# VoltTap.net
KiCad netlist of a schematic drawn in Altium Designer
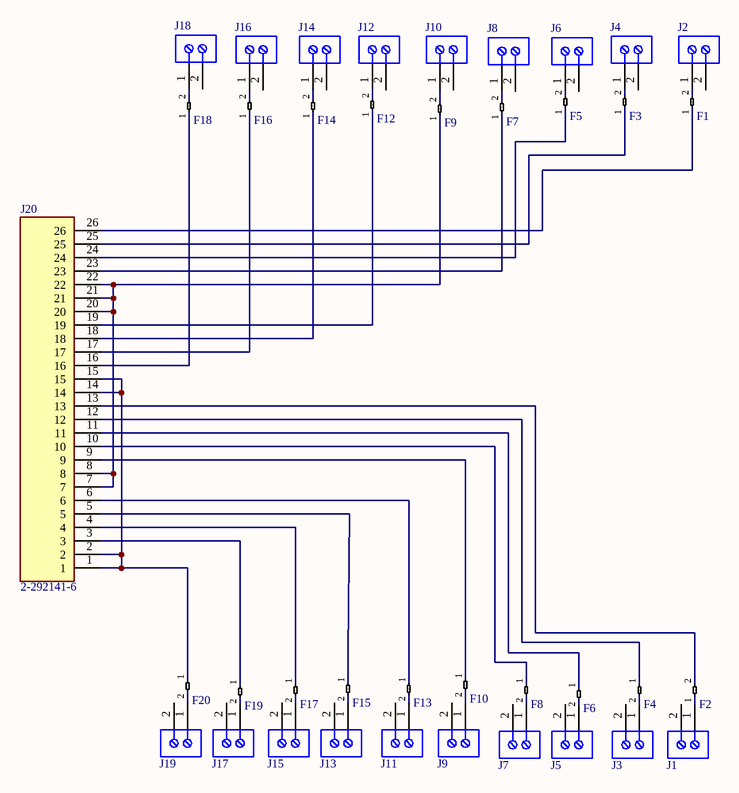
[diagram p0: VoltTap.SchDoc]

(export (version "E")
  (design (tool "Eeschema 10.0.6"))
  (components
    (comp (ref "F1") (value "C1T5") (footprint "C1T5") (libsource (lib "Integrated_Library1") (part "C1T5")))
    (comp (ref "F2") (value "C1T5") (footprint "C1T5") (libsource (lib "Integrated_Library1") (part "C1T5")))
    (comp (ref "F3") (value "C1T5") (footprint "C1T5") (libsource (lib "Integrated_Library1") (part "C1T5")))
    (comp (ref "F4") (value "C1T5") (footprint "C1T5") (libsource (lib "Integrated_Library1") (part "C1T5")))
    (comp (ref "F5") (value "C1T5") (footprint "C1T5") (libsource (lib "Integrated_Library1") (part "C1T5")))
    (comp (ref "F6") (value "C1T5") (footprint "C1T5") (libsource (lib "Integrated_Library1") (part "C1T5")))
    (comp (ref "F7") (value "C1T5") (footprint "C1T5") (libsource (lib "Integrated_Library1") (part "C1T5")))
    (comp (ref "F8") (value "C1T5") (footprint "C1T5") (libsource (lib "Integrated_Library1") (part "C1T5")))
    (comp (ref "F9") (value "C1T5") (footprint "C1T5") (libsource (lib "Integrated_Library1") (part "C1T5")))
    (comp (ref "F10") (value "C1T5") (footprint "C1T5") (libsource (lib "Integrated_Library1") (part "C1T5")))
    (comp (ref "F12") (value "C1T5") (footprint "C1T5") (libsource (lib "Integrated_Library1") (part "C1T5")))
    (comp (ref "F13") (value "C1T5") (footprint "C1T5") (libsource (lib "Integrated_Library1") (part "C1T5")))
    (comp (ref "F14") (value "C1T5") (footprint "C1T5") (libsource (lib "Integrated_Library1") (part "C1T5")))
    (comp (ref "F15") (value "C1T5") (footprint "C1T5") (libsource (lib "Integrated_Library1") (part "C1T5")))
    (comp (ref "F16") (value "C1T5") (footprint "C1T5") (libsource (lib "Integrated_Library1") (part "C1T5")))
    (comp (ref "F17") (value "C1T5") (footprint "C1T5") (libsource (lib "Integrated_Library1") (part "C1T5")))
    (comp (ref "F18") (value "C1T5") (footprint "C1T5") (libsource (lib "Integrated_Library1") (part "C1T5")))
    (comp (ref "F19") (value "C1T5") (footprint "C1T5") (libsource (lib "Integrated_Library1") (part "C1T5")))
    (comp (ref "F20") (value "C1T5") (footprint "C1T5") (libsource (lib "Integrated_Library1") (part "C1T5")))
    (comp (ref "J1")
      (value "691102710002")
      (footprint "691102710002")
      (description "Series 102 - 5.00 mm Horizontal Entry Modular with Pressure Clamp WR-TBL, 2 pin")
      (fields (field (name "MANUFACTURER") "Wurth Elektronik") (field (name "PUBLISHER") "WurthElektronik"))
      (libsource (lib "Altium Content Vault") (part "WE-CN-1P-F-TB2"))
    )
    (comp (ref "J2")
      (value "691102710002")
      (footprint "691102710002")
      (description "Series 102 - 5.00 mm Horizontal Entry Modular with Pressure Clamp WR-TBL, 2 pin")
      (fields (field (name "MANUFACTURER") "Wurth Elektronik") (field (name "PUBLISHER") "WurthElektronik"))
      (libsource (lib "Altium Content Vault") (part "WE-CN-1P-F-TB2"))
    )
    (comp (ref "J3")
      (value "691102710002")
      (footprint "691102710002")
      (description "Series 102 - 5.00 mm Horizontal Entry Modular with Pressure Clamp WR-TBL, 2 pin")
      (fields (field (name "MANUFACTURER") "Wurth Elektronik") (field (name "PUBLISHER") "WurthElektronik"))
      (libsource (lib "Altium Content Vault") (part "WE-CN-1P-F-TB2"))
    )
    (comp (ref "J4")
      (value "691102710002")
      (footprint "691102710002")
      (description "Series 102 - 5.00 mm Horizontal Entry Modular with Pressure Clamp WR-TBL, 2 pin")
      (fields (field (name "MANUFACTURER") "Wurth Elektronik") (field (name "PUBLISHER") "WurthElektronik"))
      (libsource (lib "Altium Content Vault") (part "WE-CN-1P-F-TB2"))
    )
    (comp (ref "J5")
      (value "691102710002")
      (footprint "691102710002")
      (description "Series 102 - 5.00 mm Horizontal Entry Modular with Pressure Clamp WR-TBL, 2 pin")
      (fields (field (name "MANUFACTURER") "Wurth Elektronik") (field (name "PUBLISHER") "WurthElektronik"))
      (libsource (lib "Altium Content Vault") (part "WE-CN-1P-F-TB2"))
    )
    (comp (ref "J6")
      (value "691102710002")
      (footprint "691102710002")
      (description "Series 102 - 5.00 mm Horizontal Entry Modular with Pressure Clamp WR-TBL, 2 pin")
      (fields (field (name "MANUFACTURER") "Wurth Elektronik") (field (name "PUBLISHER") "WurthElektronik"))
      (libsource (lib "Altium Content Vault") (part "WE-CN-1P-F-TB2"))
    )
    (comp (ref "J7")
      (value "691102710002")
      (footprint "691102710002")
      (description "Series 102 - 5.00 mm Horizontal Entry Modular with Pressure Clamp WR-TBL, 2 pin")
      (fields (field (name "MANUFACTURER") "Wurth Elektronik") (field (name "PUBLISHER") "WurthElektronik"))
      (libsource (lib "Altium Content Vault") (part "WE-CN-1P-F-TB2"))
    )
    (comp (ref "J8")
      (value "691102710002")
      (footprint "691102710002")
      (description "Series 102 - 5.00 mm Horizontal Entry Modular with Pressure Clamp WR-TBL, 2 pin")
      (fields (field (name "MANUFACTURER") "Wurth Elektronik") (field (name "PUBLISHER") "WurthElektronik"))
      (libsource (lib "Altium Content Vault") (part "WE-CN-1P-F-TB2"))
    )
    (comp (ref "J9")
      (value "691102710002")
      (footprint "691102710002")
      (description "Series 102 - 5.00 mm Horizontal Entry Modular with Pressure Clamp WR-TBL, 2 pin")
      (fields (field (name "MANUFACTURER") "Wurth Elektronik") (field (name "PUBLISHER") "WurthElektronik"))
      (libsource (lib "Altium Content Vault") (part "WE-CN-1P-F-TB2"))
    )
    (comp (ref "J10")
      (value "691102710002")
      (footprint "691102710002")
      (description "Series 102 - 5.00 mm Horizontal Entry Modular with Pressure Clamp WR-TBL, 2 pin")
      (fields (field (name "MANUFACTURER") "Wurth Elektronik") (field (name "PUBLISHER") "WurthElektronik"))
      (libsource (lib "Altium Content Vault") (part "WE-CN-1P-F-TB2"))
    )
    (comp (ref "J11")
      (value "691102710002")
      (footprint "691102710002")
      (description "Series 102 - 5.00 mm Horizontal Entry Modular with Pressure Clamp WR-TBL, 2 pin")
      (fields (field (name "MANUFACTURER") "Wurth Elektronik") (field (name "PUBLISHER") "WurthElektronik"))
      (libsource (lib "Altium Content Vault") (part "WE-CN-1P-F-TB2"))
    )
    (comp (ref "J12")
      (value "691102710002")
      (footprint "691102710002")
      (description "Series 102 - 5.00 mm Horizontal Entry Modular with Pressure Clamp WR-TBL, 2 pin")
      (fields (field (name "MANUFACTURER") "Wurth Elektronik") (field (name "PUBLISHER") "WurthElektronik"))
      (libsource (lib "Altium Content Vault") (part "WE-CN-1P-F-TB2"))
    )
    (comp (ref "J13")
      (value "691102710002")
      (footprint "691102710002")
      (description "Series 102 - 5.00 mm Horizontal Entry Modular with Pressure Clamp WR-TBL, 2 pin")
      (fields (field (name "MANUFACTURER") "Wurth Elektronik") (field (name "PUBLISHER") "WurthElektronik"))
      (libsource (lib "Altium Content Vault") (part "WE-CN-1P-F-TB2"))
    )
    (comp (ref "J14")
      (value "691102710002")
      (footprint "691102710002")
      (description "Series 102 - 5.00 mm Horizontal Entry Modular with Pressure Clamp WR-TBL, 2 pin")
      (fields (field (name "MANUFACTURER") "Wurth Elektronik") (field (name "PUBLISHER") "WurthElektronik"))
      (libsource (lib "Altium Content Vault") (part "WE-CN-1P-F-TB2"))
    )
    (comp (ref "J15")
      (value "691102710002")
      (footprint "691102710002")
      (description "Series 102 - 5.00 mm Horizontal Entry Modular with Pressure Clamp WR-TBL, 2 pin")
      (fields (field (name "MANUFACTURER") "Wurth Elektronik") (field (name "PUBLISHER") "WurthElektronik"))
      (libsource (lib "Altium Content Vault") (part "WE-CN-1P-F-TB2"))
    )
    (comp (ref "J16")
      (value "691102710002")
      (footprint "691102710002")
      (description "Series 102 - 5.00 mm Horizontal Entry Modular with Pressure Clamp WR-TBL, 2 pin")
      (fields (field (name "MANUFACTURER") "Wurth Elektronik") (field (name "PUBLISHER") "WurthElektronik"))
      (libsource (lib "Altium Content Vault") (part "WE-CN-1P-F-TB2"))
    )
    (comp (ref "J17")
      (value "691102710002")
      (footprint "691102710002")
      (description "Series 102 - 5.00 mm Horizontal Entry Modular with Pressure Clamp WR-TBL, 2 pin")
      (fields (field (name "MANUFACTURER") "Wurth Elektronik") (field (name "PUBLISHER") "WurthElektronik"))
      (libsource (lib "Altium Content Vault") (part "WE-CN-1P-F-TB2"))
    )
    (comp (ref "J18")
      (value "691102710002")
      (footprint "691102710002")
      (description "Series 102 - 5.00 mm Horizontal Entry Modular with Pressure Clamp WR-TBL, 2 pin")
      (fields (field (name "MANUFACTURER") "Wurth Elektronik") (field (name "PUBLISHER") "WurthElektronik"))
      (libsource (lib "Altium Content Vault") (part "WE-CN-1P-F-TB2"))
    )
    (comp (ref "J19")
      (value "691102710002")
      (footprint "691102710002")
      (description "Series 102 - 5.00 mm Horizontal Entry Modular with Pressure Clamp WR-TBL, 2 pin")
      (fields (field (name "MANUFACTURER") "Wurth Elektronik") (field (name "PUBLISHER") "WurthElektronik"))
      (libsource (lib "Altium Content Vault") (part "WE-CN-1P-F-TB2"))
    )
    (comp (ref "J20")
      (value "2-292141-6")
      (footprint "TE_2-292141-6")
      (fields (field (name "MF") "{'manufacturer': 'TE Connectivity'}"))
      (libsource (lib "2-292141-6") (part "2-292141-6"))
    )
  )
  (nets
    (net (code "1") (name "Net-(F1-Pad1)") (class "Default")
      (node (ref "F1") (pin "1") (pinfunction "1_1") (pintype "passive"))
      (node (ref "J20") (pin "26") (pinfunction "26_26") (pintype "passive"))
    )
    (net (code "2") (name "Net-(F1-Pad2)") (class "Default")
      (node (ref "F1") (pin "2") (pinfunction "2_2") (pintype "passive"))
      (node (ref "J2") (pin "1") (pinfunction "1_1") (pintype "passive"))
    )
    (net (code "3") (name "Net-(F2-Pad1)") (class "Default")
      (node (ref "F2") (pin "1") (pinfunction "1_1") (pintype "passive"))
      (node (ref "J1") (pin "1") (pinfunction "1_1") (pintype "passive"))
    )
    (net (code "4") (name "Net-(F2-Pad2)") (class "Default")
      (node (ref "F2") (pin "2") (pinfunction "2_2") (pintype "passive"))
      (node (ref "J20") (pin "13") (pinfunction "13_13") (pintype "passive"))
    )
    (net (code "5") (name "Net-(F3-Pad1)") (class "Default")
      (node (ref "F3") (pin "1") (pinfunction "1_1") (pintype "passive"))
      (node (ref "J20") (pin "25") (pinfunction "25_25") (pintype "passive"))
    )
    (net (code "6") (name "Net-(F3-Pad2)") (class "Default")
      (node (ref "F3") (pin "2") (pinfunction "2_2") (pintype "passive"))
      (node (ref "J4") (pin "1") (pinfunction "1_1") (pintype "passive"))
    )
    (net (code "7") (name "Net-(F4-Pad1)") (class "Default")
      (node (ref "F4") (pin "1") (pinfunction "1_1") (pintype "passive"))
      (node (ref "J20") (pin "12") (pinfunction "12_12") (pintype "passive"))
    )
    (net (code "8") (name "Net-(F4-Pad2)") (class "Default")
      (node (ref "F4") (pin "2") (pinfunction "2_2") (pintype "passive"))
      (node (ref "J3") (pin "1") (pinfunction "1_1") (pintype "passive"))
    )
    (net (code "9") (name "Net-(F5-Pad1)") (class "Default")
      (node (ref "F5") (pin "1") (pinfunction "1_1") (pintype "passive"))
      (node (ref "J20") (pin "24") (pinfunction "24_24") (pintype "passive"))
    )
    (net (code "10") (name "Net-(F5-Pad2)") (class "Default")
      (node (ref "F5") (pin "2") (pinfunction "2_2") (pintype "passive"))
      (node (ref "J6") (pin "1") (pinfunction "1_1") (pintype "passive"))
    )
    (net (code "11") (name "Net-(F6-Pad1)") (class "Default")
      (node (ref "F6") (pin "1") (pinfunction "1_1") (pintype "passive"))
      (node (ref "J20") (pin "11") (pinfunction "11_11") (pintype "passive"))
    )
    (net (code "12") (name "Net-(F6-Pad2)") (class "Default")
      (node (ref "F6") (pin "2") (pinfunction "2_2") (pintype "passive"))
      (node (ref "J5") (pin "1") (pinfunction "1_1") (pintype "passive"))
    )
    (net (code "13") (name "Net-(F7-Pad1)") (class "Default")
      (node (ref "F7") (pin "1") (pinfunction "1_1") (pintype "passive"))
      (node (ref "J20") (pin "23") (pinfunction "23_23") (pintype "passive"))
    )
    (net (code "14") (name "Net-(F7-Pad2)") (class "Default")
      (node (ref "F7") (pin "2") (pinfunction "2_2") (pintype "passive"))
      (node (ref "J8") (pin "1") (pinfunction "1_1") (pintype "passive"))
    )
    (net (code "15") (name "Net-(F8-Pad1)") (class "Default")
      (node (ref "F8") (pin "1") (pinfunction "1_1") (pintype "passive"))
      (node (ref "J20") (pin "10") (pinfunction "10_10") (pintype "passive"))
    )
    (net (code "16") (name "Net-(F8-Pad2)") (class "Default")
      (node (ref "F8") (pin "2") (pinfunction "2_2") (pintype "passive"))
      (node (ref "J7") (pin "1") (pinfunction "1_1") (pintype "passive"))
    )
    (net (code "17") (name "Net-(F9-Pad1)") (class "Default")
      (node (ref "F9") (pin "1") (pinfunction "1_1") (pintype "passive"))
      (node (ref "J20") (pin "20") (pinfunction "20_20") (pintype "passive"))
      (node (ref "J20") (pin "21") (pinfunction "21_21") (pintype "passive"))
      (node (ref "J20") (pin "22") (pinfunction "22_22") (pintype "passive"))
      (node (ref "J20") (pin "7") (pinfunction "7_7") (pintype "passive"))
      (node (ref "J20") (pin "8") (pinfunction "8_8") (pintype "passive"))
    )
    (net (code "18") (name "Net-(F9-Pad2)") (class "Default")
      (node (ref "F9") (pin "2") (pinfunction "2_2") (pintype "passive"))
      (node (ref "J10") (pin "1") (pinfunction "1_1") (pintype "passive"))
    )
    (net (code "19") (name "Net-(F10-Pad1)") (class "Default")
      (node (ref "F10") (pin "1") (pinfunction "1_1") (pintype "passive"))
      (node (ref "J20") (pin "9") (pinfunction "9_9") (pintype "passive"))
    )
    (net (code "20") (name "Net-(F10-Pad2)") (class "Default")
      (node (ref "F10") (pin "2") (pinfunction "2_2") (pintype "passive"))
      (node (ref "J9") (pin "1") (pinfunction "1_1") (pintype "passive"))
    )
    (net (code "21") (name "Net-(F12-Pad1)") (class "Default")
      (node (ref "F12") (pin "1") (pinfunction "1_1") (pintype "passive"))
      (node (ref "J20") (pin "19") (pinfunction "19_19") (pintype "passive"))
    )
    (net (code "22") (name "Net-(F12-Pad2)") (class "Default")
      (node (ref "F12") (pin "2") (pinfunction "2_2") (pintype "passive"))
      (node (ref "J12") (pin "1") (pinfunction "1_1") (pintype "passive"))
    )
    (net (code "23") (name "Net-(F13-Pad1)") (class "Default")
      (node (ref "F13") (pin "1") (pinfunction "1_1") (pintype "passive"))
      (node (ref "J20") (pin "6") (pinfunction "6_6") (pintype "passive"))
    )
    (net (code "24") (name "Net-(F13-Pad2)") (class "Default")
      (node (ref "F13") (pin "2") (pinfunction "2_2") (pintype "passive"))
      (node (ref "J11") (pin "1") (pinfunction "1_1") (pintype "passive"))
    )
    (net (code "25") (name "Net-(F14-Pad1)") (class "Default")
      (node (ref "F14") (pin "1") (pinfunction "1_1") (pintype "passive"))
      (node (ref "J20") (pin "18") (pinfunction "18_18") (pintype "passive"))
    )
    (net (code "26") (name "Net-(F14-Pad2)") (class "Default")
      (node (ref "F14") (pin "2") (pinfunction "2_2") (pintype "passive"))
      (node (ref "J14") (pin "1") (pinfunction "1_1") (pintype "passive"))
    )
    (net (code "27") (name "Net-(F15-Pad1)") (class "Default")
      (node (ref "F15") (pin "1") (pinfunction "1_1") (pintype "passive"))
      (node (ref "J20") (pin "5") (pinfunction "5_5") (pintype "passive"))
    )
    (net (code "28") (name "Net-(F15-Pad2)") (class "Default")
      (node (ref "F15") (pin "2") (pinfunction "2_2") (pintype "passive"))
      (node (ref "J13") (pin "1") (pinfunction "1_1") (pintype "passive"))
    )
    (net (code "29") (name "Net-(F16-Pad1)") (class "Default")
      (node (ref "F16") (pin "1") (pinfunction "1_1") (pintype "passive"))
      (node (ref "J20") (pin "17") (pinfunction "17_17") (pintype "passive"))
    )
    (net (code "30") (name "Net-(F16-Pad2)") (class "Default")
      (node (ref "F16") (pin "2") (pinfunction "2_2") (pintype "passive"))
      (node (ref "J16") (pin "1") (pinfunction "1_1") (pintype "passive"))
    )
    (net (code "31") (name "Net-(F17-Pad1)") (class "Default")
      (node (ref "F17") (pin "1") (pinfunction "1_1") (pintype "passive"))
      (node (ref "J20") (pin "4") (pinfunction "4_4") (pintype "passive"))
    )
    (net (code "32") (name "Net-(F17-Pad2)") (class "Default")
      (node (ref "F17") (pin "2") (pinfunction "2_2") (pintype "passive"))
      (node (ref "J15") (pin "1") (pinfunction "1_1") (pintype "passive"))
    )
    (net (code "33") (name "Net-(F18-Pad1)") (class "Default")
      (node (ref "F18") (pin "1") (pinfunction "1_1") (pintype "passive"))
      (node (ref "J20") (pin "16") (pinfunction "16_16") (pintype "passive"))
    )
    (net (code "34") (name "Net-(F18-Pad2)") (class "Default")
      (node (ref "F18") (pin "2") (pinfunction "2_2") (pintype "passive"))
      (node (ref "J18") (pin "1") (pinfunction "1_1") (pintype "passive"))
    )
    (net (code "35") (name "Net-(F19-Pad1)") (class "Default")
      (node (ref "F19") (pin "1") (pinfunction "1_1") (pintype "passive"))
      (node (ref "J20") (pin "3") (pinfunction "3_3") (pintype "passive"))
    )
    (net (code "36") (name "Net-(F19-Pad2)") (class "Default")
      (node (ref "F19") (pin "2") (pinfunction "2_2") (pintype "passive"))
      (node (ref "J17") (pin "1") (pinfunction "1_1") (pintype "passive"))
    )
    (net (code "37") (name "Net-(F20-Pad1)") (class "Default")
      (node (ref "F20") (pin "1") (pinfunction "1_1") (pintype "passive"))
      (node (ref "J20") (pin "1") (pinfunction "1_1") (pintype "passive"))
      (node (ref "J20") (pin "14") (pinfunction "14_14") (pintype "passive"))
      (node (ref "J20") (pin "15") (pinfunction "15_15") (pintype "passive"))
      (node (ref "J20") (pin "2") (pinfunction "2_2") (pintype "passive"))
    )
    (net (code "38") (name "Net-(F20-Pad2)") (class "Default")
      (node (ref "F20") (pin "2") (pinfunction "2_2") (pintype "passive"))
      (node (ref "J19") (pin "1") (pinfunction "1_1") (pintype "passive"))
    )
    (net (code "39") (name "unconnected-(J1-Pad2)") (class "Default")
      (node (ref "J1") (pin "2") (pinfunction "2_2") (pintype "passive"))
    )
    (net (code "40") (name "unconnected-(J2-Pad2)") (class "Default")
      (node (ref "J2") (pin "2") (pinfunction "2_2") (pintype "passive"))
    )
    (net (code "41") (name "unconnected-(J3-Pad2)") (class "Default")
      (node (ref "J3") (pin "2") (pinfunction "2_2") (pintype "passive"))
    )
    (net (code "42") (name "unconnected-(J4-Pad2)") (class "Default")
      (node (ref "J4") (pin "2") (pinfunction "2_2") (pintype "passive"))
    )
    (net (code "43") (name "unconnected-(J5-Pad2)") (class "Default")
      (node (ref "J5") (pin "2") (pinfunction "2_2") (pintype "passive"))
    )
    (net (code "44") (name "unconnected-(J6-Pad2)") (class "Default")
      (node (ref "J6") (pin "2") (pinfunction "2_2") (pintype "passive"))
    )
    (net (code "45") (name "unconnected-(J7-Pad2)") (class "Default")
      (node (ref "J7") (pin "2") (pinfunction "2_2") (pintype "passive"))
    )
    (net (code "46") (name "unconnected-(J8-Pad2)") (class "Default")
      (node (ref "J8") (pin "2") (pinfunction "2_2") (pintype "passive"))
    )
    (net (code "47") (name "unconnected-(J9-Pad2)") (class "Default")
      (node (ref "J9") (pin "2") (pinfunction "2_2") (pintype "passive"))
    )
    (net (code "48") (name "unconnected-(J10-Pad2)") (class "Default")
      (node (ref "J10") (pin "2") (pinfunction "2_2") (pintype "passive"))
    )
    (net (code "49") (name "unconnected-(J11-Pad2)") (class "Default")
      (node (ref "J11") (pin "2") (pinfunction "2_2") (pintype "passive"))
    )
    (net (code "50") (name "unconnected-(J12-Pad2)") (class "Default")
      (node (ref "J12") (pin "2") (pinfunction "2_2") (pintype "passive"))
    )
    (net (code "51") (name "unconnected-(J13-Pad2)") (class "Default")
      (node (ref "J13") (pin "2") (pinfunction "2_2") (pintype "passive"))
    )
    (net (code "52") (name "unconnected-(J14-Pad2)") (class "Default")
      (node (ref "J14") (pin "2") (pinfunction "2_2") (pintype "passive"))
    )
    (net (code "53") (name "unconnected-(J15-Pad2)") (class "Default")
      (node (ref "J15") (pin "2") (pinfunction "2_2") (pintype "passive"))
    )
    (net (code "54") (name "unconnected-(J16-Pad2)") (class "Default")
      (node (ref "J16") (pin "2") (pinfunction "2_2") (pintype "passive"))
    )
    (net (code "55") (name "unconnected-(J17-Pad2)") (class "Default")
      (node (ref "J17") (pin "2") (pinfunction "2_2") (pintype "passive"))
    )
    (net (code "56") (name "unconnected-(J18-Pad2)") (class "Default")
      (node (ref "J18") (pin "2") (pinfunction "2_2") (pintype "passive"))
    )
    (net (code "57") (name "unconnected-(J19-Pad2)") (class "Default")
      (node (ref "J19") (pin "2") (pinfunction "2_2") (pintype "passive"))
    )
  )
)
